# Encoder-Sheet.net
KiCad netlist of a schematic drawn in Altium Designer
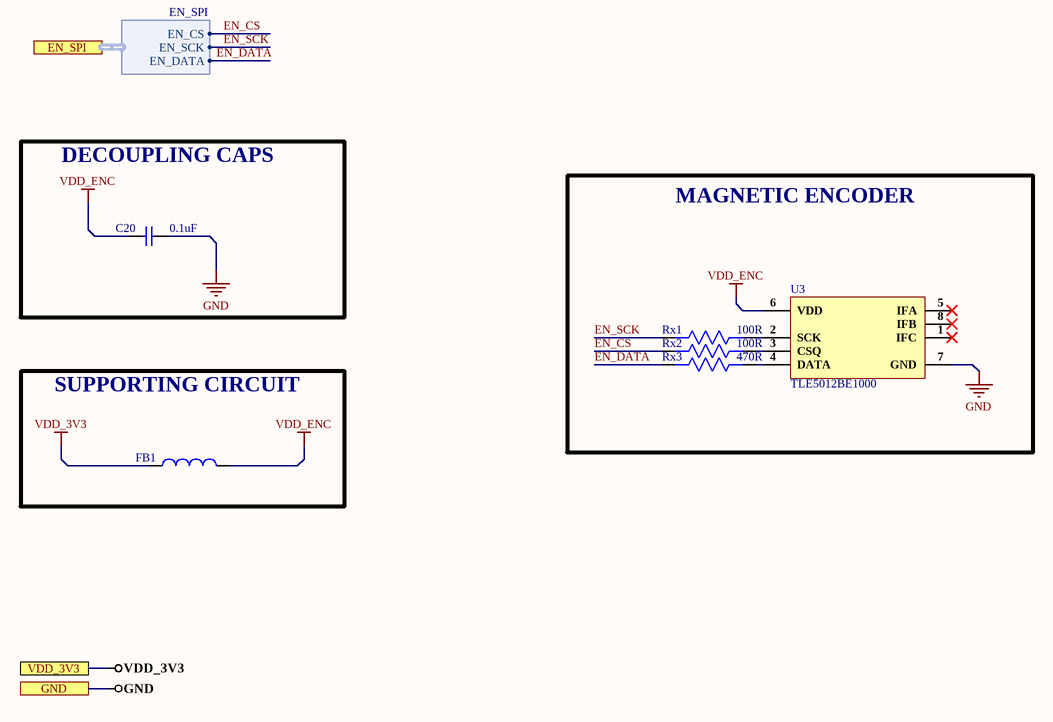
[diagram p0: Encoder-Sheet.SchDoc]

(export (version "E")
  (design (tool "Eeschema 10.0.6"))
  (components
    (comp (ref "C20")
      (value "0.1uF")
      (footprint "Cap 0603")
      (description "Cap Ceramic 0.1uF 50VDC X7R 10% SMD 0603 Paper T/R")
      (fields
        (field (name "MANUFACTURER") "Samsung")
        (field (name "MANUFACTURER PART NUMBER") "CL10B104KB8NNNC")
      )
      (libsource (lib "Cole_Benson") (part "CL10B104KB8NNNC"))
    )
    (comp (ref "FB1")
      (value "MPZ1608S121ATDH5")
      (footprint "MPZ1608S121ATDH5")
      (description "Ferrite Beads Multi-Layer 120Ohm 25% 100MHz 2A 45mOhm DCR 0603 Automotive T/R")
      (fields (field (name "MANUFACTURER") "TDK") (field (name "TOLERANCE") "25%"))
      (libsource (lib "Cole_Benson") (part "MPZ1608S121ATDH5"))
    )
    (comp (ref "Rx1")
      (value "100R")
      (footprint "Res0603")
      (description "RES SMD 100 OHM 1% 1/10W 0603")
      (fields
        (field (name "MANUFACTURER") "Yageo")
        (field (name "MANUFACTURER PART NUMBER") "RC0603FR-07100RL")
      )
      (libsource (lib "Cole_Benson") (part "RC0603FR-07100RL"))
    )
    (comp (ref "Rx2")
      (value "100R")
      (footprint "Res0603")
      (description "RES SMD 100 OHM 1% 1/10W 0603")
      (fields
        (field (name "MANUFACTURER") "Yageo")
        (field (name "MANUFACTURER PART NUMBER") "RC0603FR-07100RL")
      )
      (libsource (lib "Cole_Benson") (part "RC0603FR-07100RL"))
    )
    (comp (ref "Rx3")
      (value "470R")
      (footprint "Res0603")
      (description "RES SMD 470 OHM 50 V, 0603 100 mW,  1%, RC Series")
      (fields
        (field (name "MANUFACTURER") "Yageo")
        (field (name "MANUFACTURER PART NUMBER") "RC0603FR-07470RL")
      )
      (libsource (lib "Cole_Benson") (part "RC0603FR-07470RL"))
    )
    (comp (ref "U3")
      (value "TLE5012BE1000")
      (footprint "PG-DSO-8")
      (description "SENSOR ANGLE 360DEG SMD")
      (fields (field (name "MANUFACTURER") "Infineon"))
      (libsource (lib "Cole_Benson") (part "TLE5012BE1000"))
    )
  )
  (nets
    (net (code "2") (name "/EN_CS") (class "Default") (node (ref "Rx2") (pin "2") (pintype "passive")))
    (net (code "3") (name "/EN_DATA") (class "Default") (node (ref "Rx3") (pin "2") (pintype "passive")))
    (net (code "4") (name "/EN_SCK") (class "Default") (node (ref "Rx1") (pin "2") (pintype "passive")))
    (net (code "6") (name "GND") (class "Default")
      (node (ref "C20") (pin "2") (pinfunction "2_2") (pintype "passive"))
      (node (ref "U3") (pin "7") (pinfunction "GND_7") (pintype "passive"))
    )
    (net (code "7") (name "Net-(U3-CSQ)") (class "Default")
      (node (ref "Rx2") (pin "1") (pintype "passive"))
      (node (ref "U3") (pin "3") (pinfunction "CSQ_3") (pintype "passive"))
    )
    (net (code "8") (name "Net-(U3-DATA)") (class "Default")
      (node (ref "Rx3") (pin "1") (pintype "passive"))
      (node (ref "U3") (pin "4") (pinfunction "DATA_4") (pintype "passive"))
    )
    (net (code "9") (name "Net-(U3-SCK)") (class "Default")
      (node (ref "Rx1") (pin "1") (pintype "passive"))
      (node (ref "U3") (pin "2") (pinfunction "SCK_2") (pintype "passive"))
    )
    (net (code "10") (name "VDD_3V3") (class "Default")
      (node (ref "FB1") (pin "1") (pinfunction "1_1") (pintype "passive"))
    )
    (net (code "11") (name "VDD_ENC") (class "Default")
      (node (ref "C20") (pin "1") (pinfunction "1_1") (pintype "passive"))
      (node (ref "FB1") (pin "2") (pinfunction "2_2") (pintype "passive"))
      (node (ref "U3") (pin "6") (pinfunction "VDD_6") (pintype "passive"))
    )
    (net (code "12") (name "unconnected-(U3-IFA-Pad5)") (class "Default")
      (node (ref "U3") (pin "5") (pinfunction "IFA_5") (pintype "passive+no_connect"))
    )
    (net (code "13") (name "unconnected-(U3-IFB-Pad8)") (class "Default")
      (node (ref "U3") (pin "8") (pinfunction "IFB_8") (pintype "passive+no_connect"))
    )
    (net (code "14") (name "unconnected-(U3-IFC-Pad1)") (class "Default")
      (node (ref "U3") (pin "1") (pinfunction "IFC_1") (pintype "passive+no_connect"))
    )
  )
)
